# KiemSoat.net
KiCad netlist of a schematic drawn in Altium Designer
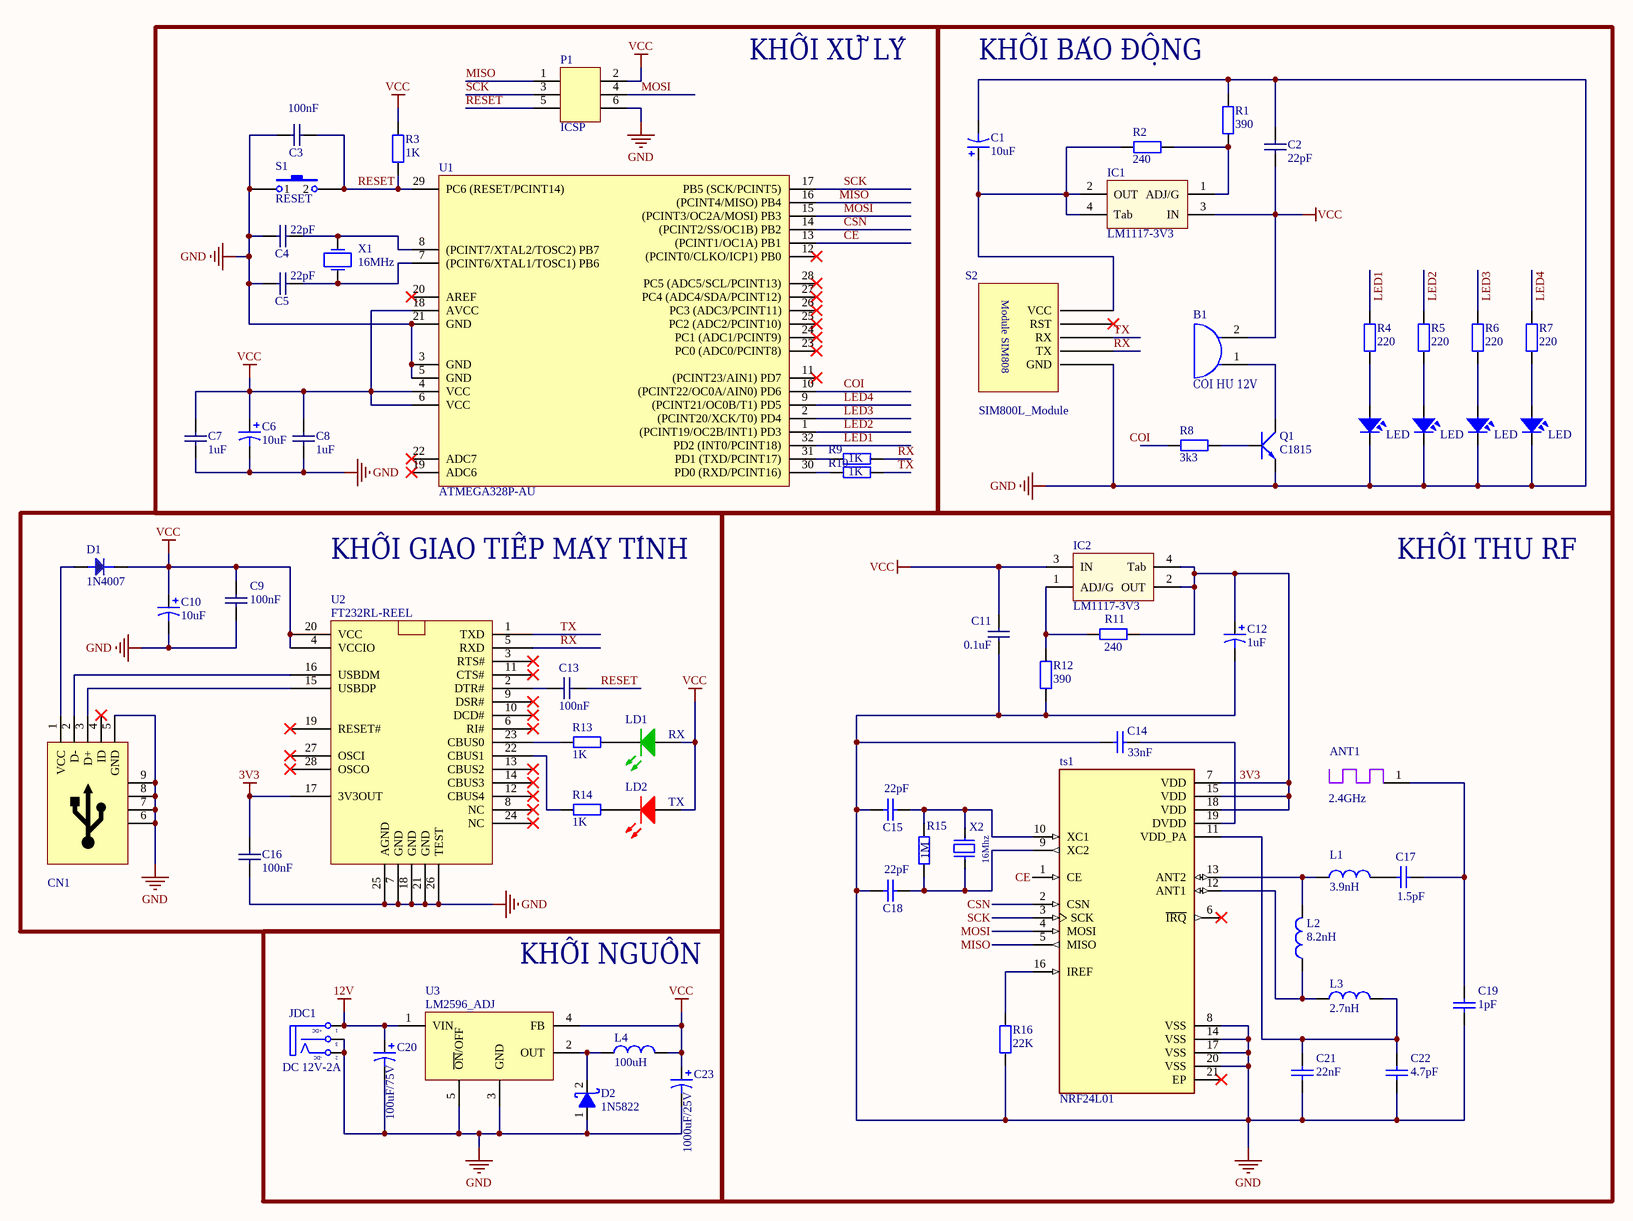
[diagram p0: KiemSoat.SchDoc]

(export (version "E")
  (design (tool "Eeschema 10.0.6"))
  (components
    (comp (ref "ANT1")
      (value "2.4GHz")
      (footprint "PATCH ANTEN 2.45GHZ")
      (description "PCB ANTENNA 2.45GHZ")
      (libsource (lib "BYTECH_HW_LIB_2019 (1)") (part "PCB antenna 2.45GHZ"))
    )
    (comp (ref "B1")
      (value "CÒI HÚ 12V")
      (footprint "Buzzer")
      (description "Buzzer")
      (libsource (lib "Cty1") (part "BUZZER"))
    )
    (comp (ref "C1")
      (value "10uF")
      (footprint "CAP_0805")
      (description "Polarized Capacitor (Axial)")
      (fields (field (name "PUBLISHER") "Altium Limited"))
      (libsource (lib "My Library") (part "Cap Pol 5mm"))
    )
    (comp (ref "C2")
      (value "22pF")
      (footprint "thuvien_altium:CAPC0805")
      (description "capacitor non polar")
      (libsource (lib "thuvien_altium") (part "capacitor_non_polar"))
    )
    (comp (ref "C3")
      (value "100nF")
      (footprint "thuvien_altium:CAPC0805")
      (description "capacitor non polar")
      (libsource (lib "thuvien_altium") (part "capacitor_non_polar"))
    )
    (comp (ref "C4")
      (value "22pF")
      (footprint "thuvien_altium:CAPC0805")
      (description "capacitor non polar")
      (libsource (lib "thuvien_altium") (part "capacitor_non_polar"))
    )
    (comp (ref "C5")
      (value "22pF")
      (footprint "thuvien_altium:CAPC0805")
      (description "capacitor non polar")
      (libsource (lib "thuvien_altium") (part "capacitor_non_polar"))
    )
    (comp (ref "C6")
      (value "10uF")
      (footprint "thuvien_altium:CAP1206_TANTALUM_YELLOW")
      (description "CAP TANT 10UF 16V 10% 1206")
      (fields (field (name "TOLERANCE") "±10%"))
      (libsource (lib "thuvien_altium") (part "T491A106K016AT"))
    )
    (comp (ref "C7")
      (value "1uF")
      (footprint "thuvien_altium:CAP0603")
      (description "capacitor non polar")
      (libsource (lib "thuvien_altium") (part "capacitor_non_polar"))
    )
    (comp (ref "C8")
      (value "1uF")
      (footprint "thuvien_altium:CAP0603")
      (description "capacitor non polar")
      (libsource (lib "thuvien_altium") (part "capacitor_non_polar"))
    )
    (comp (ref "C9")
      (value "100nF")
      (footprint "thuvien_altium:CAP0603")
      (description "capacitor non polar")
      (libsource (lib "thuvien_altium") (part "capacitor_non_polar"))
    )
    (comp (ref "C10")
      (value "10uF")
      (footprint "thuvien_altium:CAP1206_TANTALUM_YELLOW")
      (description "CAP TANT 10UF 16V 10% 1206")
      (fields (field (name "TOLERANCE") "±10%"))
      (libsource (lib "thuvien_altium") (part "T491A106K016AT"))
    )
    (comp (ref "C11")
      (value "0.1uF")
      (footprint "thuvien_altium:CAPC0805")
      (description "capacitor non polar")
      (libsource (lib "thuvien_altium") (part "capacitor_non_polar"))
    )
    (comp (ref "C12")
      (value "1uF")
      (footprint "CAP_0805")
      (description "Polarized Capacitor (Axial)")
      (fields (field (name "PUBLISHER") "Altium Limited"))
      (libsource (lib "My Library") (part "Cap Pol 5mm"))
    )
    (comp (ref "C13")
      (value "100nF")
      (footprint "thuvien_altium:CAP0603")
      (description "capacitor non polar")
      (libsource (lib "thuvien_altium") (part "capacitor_non_polar"))
    )
    (comp (ref "C14")
      (value "33nF")
      (footprint "CAPC0805")
      (description "Capacitor")
      (fields (field (name "PUBLISHER") "Altium Limited"))
      (libsource (lib "My Library") (part "CapCeramic"))
    )
    (comp (ref "C15")
      (value "22pF")
      (footprint "CAPC0805")
      (description "Capacitor")
      (fields (field (name "PUBLISHER") "Altium Limited"))
      (libsource (lib "My Library") (part "CapCeramic"))
    )
    (comp (ref "C16")
      (value "100nF")
      (footprint "thuvien_altium:CAP0603")
      (description "capacitor non polar")
      (libsource (lib "thuvien_altium") (part "capacitor_non_polar"))
    )
    (comp (ref "C17")
      (value "1.5pF")
      (footprint "CAPC0805")
      (description "Capacitor")
      (fields (field (name "PUBLISHER") "Altium Limited"))
      (libsource (lib "My Library") (part "CapCeramic"))
    )
    (comp (ref "C18")
      (value "22pF")
      (footprint "CAPC0805")
      (description "Capacitor")
      (fields (field (name "PUBLISHER") "Altium Limited"))
      (libsource (lib "My Library") (part "CapCeramic"))
    )
    (comp (ref "C19")
      (value "1pF")
      (footprint "CAPC0805")
      (description "Capacitor")
      (fields (field (name "PUBLISHER") "Altium Limited"))
      (libsource (lib "My Library") (part "CapCeramic"))
    )
    (comp (ref "C20")
      (value "100uF/75V")
      (footprint "CAP-ALU-SMD-G")
      (description "Polarized Capacitor (Axial)")
      (fields (field (name "PUBLISHER") "Altium Limited"))
      (libsource (lib "My Library") (part "Cap Pol 5mm"))
    )
    (comp (ref "C21")
      (value "22nF")
      (footprint "CAPC0805")
      (description "Capacitor")
      (fields (field (name "PUBLISHER") "Altium Limited"))
      (libsource (lib "My Library") (part "CapCeramic"))
    )
    (comp (ref "C22")
      (value "4.7pF")
      (footprint "CAPC0805")
      (description "Capacitor")
      (fields (field (name "PUBLISHER") "Altium Limited"))
      (libsource (lib "My Library") (part "CapCeramic"))
    )
    (comp (ref "C23")
      (value "1000uF/25V")
      (footprint "CAP-ALU-SMD-G")
      (description "Polarized Capacitor (Axial)")
      (fields (field (name "PUBLISHER") "Altium Limited"))
      (libsource (lib "My Library") (part "Cap Pol 5mm"))
    )
    (comp (ref "CN1")
      (value "690-005-299-043")
      (footprint "thuvien_altium:USB-B-MINI_690-005-299-043")
      (description "CONN MINI USB RCPT RA TYPE B SMD")
      (fields (field (name "MANUFACTURER") "EDAC Inc."))
      (libsource (lib "thuvien_altium") (part "USB_690-005-299-043"))
    )
    (comp (ref "D1")
      (value "1N4007")
      (footprint "thuvien_altium:DO-214AC")
      (description "diode")
      (libsource (lib "thuvien_altium") (part "diode"))
    )
    (comp (ref "D2")
      (value "1N5822")
      (footprint "SM-DIODE")
      (description "Schottky Rectifiers")
      (libsource (lib "My Library") (part "1N5822"))
    )
    (comp (ref "IC1")
      (value "LM1117-3V3")
      (footprint "SOT223-4N")
      (description "3v3")
      (libsource (lib "") (part "LM1117_1_1"))
    )
    (comp (ref "IC2")
      (value "LM1117-3V3")
      (footprint "SOT223-4N")
      (description "3v3")
      (libsource (lib "[Devzone.vn]_SchLibrary") (part "LM1117_1"))
    )
    (comp (ref "JDC1")
      (value "DC 12V-2A")
      (footprint "DC-IN")
      (description "Jac DC input")
      (libsource (lib "[Devzone.vn]_SchLibrary") (part "DCIN"))
    )
    (comp (ref "L1")
      (value "3.9nH")
      (footprint "INDC_DR127-1")
      (description "Inductor")
      (libsource (lib "My Library") (part "L1"))
    )
    (comp (ref "L2")
      (value "8.2nH")
      (footprint "INDC_DR127-1")
      (description "Inductor")
      (libsource (lib "My Library") (part "L1"))
    )
    (comp (ref "L3")
      (value "2.7nH")
      (footprint "INDC_DR127-1")
      (description "Inductor")
      (libsource (lib "My Library") (part "L1"))
    )
    (comp (ref "L4")
      (value "100uH")
      (footprint "Inductor_SMD")
      (description "Inductor")
      (libsource (lib "My Library") (part "Inductor"))
    )
    (comp (ref "LD1")
      (value "RX")
      (footprint "thuvien_altium:LED_SMD0603_GREEN")
      (description "LED GREEN CLEAR 0603 SMD")
      (libsource (lib "thuvien_altium") (part "LED_LTST-C191KGKT"))
    )
    (comp (ref "LD2")
      (value "TX")
      (footprint "thuvien_altium:LED_SMD0603_RED")
      (description "LED RED CLEAR 0603 SMD")
      (fields
        (field (name "MANUFACTURER") "Lite-On Inc.")
        (field (name "MANUFACTURER PART NUMBER") "LTST-C191KRKT")
      )
      (libsource (lib "thuvien_altium") (part "LED_LTST-C191KRKT"))
    )
    (comp (ref "LED1")
      (value "LED")
      (footprint "LED-RED-0805")
      (description "LED Single colour Green and Red")
      (libsource (lib "My Library") (part "LED"))
    )
    (comp (ref "LED2")
      (value "LED")
      (footprint "LED-RED-0805")
      (description "LED Single colour Green and Red")
      (libsource (lib "My Library") (part "LED"))
    )
    (comp (ref "LED3")
      (value "LED")
      (footprint "LED-RED-0805")
      (description "LED Single colour Green and Red")
      (libsource (lib "My Library") (part "LED"))
    )
    (comp (ref "LED4")
      (value "LED")
      (footprint "LED-RED-0805")
      (description "LED Single colour Green and Red")
      (libsource (lib "My Library") (part "LED"))
    )
    (comp (ref "P1")
      (value "ICSP")
      (footprint "thuvien_altium:HDR_M_2X3_2.54")
      (libsource (lib "thuvien_altium") (part "header_2x3pins"))
    )
    (comp (ref "Q1")
      (value "C1815")
      (footprint "SOT23B")
      (description "NPN 600mW, ECB")
      (libsource (lib "syhaunguyen") (part "C1815"))
    )
    (comp (ref "R1")
      (value "390")
      (footprint "RES_SMD_0805")
      (description "Resistor 1/4W")
      (libsource (lib "My Library") (part "R1/4W"))
    )
    (comp (ref "R2")
      (value "240")
      (footprint "RES_SMD_0805")
      (description "Resistor 1/4W")
      (libsource (lib "My Library") (part "R1/4W"))
    )
    (comp (ref "R3")
      (value "1K")
      (footprint "RES_SMD_0805")
      (description "Resistor 1/4W")
      (libsource (lib "My Library") (part "R1/4W"))
    )
    (comp (ref "R4")
      (value "220")
      (footprint "RES_SMD_0805")
      (description "Resistor 1/4W")
      (libsource (lib "My Library") (part "R1/4W"))
    )
    (comp (ref "R5")
      (value "220")
      (footprint "RES_SMD_0805")
      (description "Resistor 1/4W")
      (libsource (lib "My Library") (part "R1/4W"))
    )
    (comp (ref "R6")
      (value "220")
      (footprint "RES_SMD_0805")
      (description "Resistor 1/4W")
      (libsource (lib "My Library") (part "R1/4W"))
    )
    (comp (ref "R7")
      (value "220")
      (footprint "RES_SMD_0805")
      (description "Resistor 1/4W")
      (libsource (lib "My Library") (part "R1/4W"))
    )
    (comp (ref "R8")
      (value "3k3")
      (footprint "RES_SMD_0805")
      (description "Resistor 1/4W")
      (libsource (lib "My Library") (part "R1/4W"))
    )
    (comp (ref "R9")
      (value "1K")
      (footprint "RES_SMD_0805")
      (description "Resistor 1/4W")
      (libsource (lib "My Library") (part "R1/4W"))
    )
    (comp (ref "R10")
      (value "1K")
      (footprint "RES_SMD_0805")
      (description "Resistor 1/4W")
      (libsource (lib "My Library") (part "R1/4W"))
    )
    (comp (ref "R11")
      (value "240")
      (footprint "RES_SMD_0805")
      (description "Resistor 1/4W")
      (libsource (lib "My Library") (part "R1/4W"))
    )
    (comp (ref "R12")
      (value "390")
      (footprint "RES_SMD_0805")
      (description "Resistor 1/4W")
      (libsource (lib "My Library") (part "R1/4W"))
    )
    (comp (ref "R13")
      (value "1K")
      (footprint "RES_SMD_0805")
      (description "Resistor 1/4W")
      (libsource (lib "My Library") (part "R1/4W"))
    )
    (comp (ref "R14")
      (value "1K")
      (footprint "RES_SMD_0805")
      (description "Resistor 1/4W")
      (libsource (lib "My Library") (part "R1/4W"))
    )
    (comp (ref "R15")
      (value "1M")
      (footprint "RES_SMD_0805")
      (description "Resistor 1/4W")
      (libsource (lib "My Library") (part "R1/4W"))
    )
    (comp (ref "R16")
      (value "22K")
      (footprint "RES_SMD_0805")
      (description "Resistor 1/4W")
      (libsource (lib "My Library") (part "R1/4W"))
    )
    (comp (ref "S1")
      (value "RESET")
      (footprint "thuvien_altium:SW_B3U-1000P")
      (description "Switch")
      (fields (field (name "PUBLISHER") "Altium Limited"))
      (libsource (lib "thuvien_altium") (part "SW-PB-2pin"))
    )
    (comp (ref "S2")
      (value "SIM800L_Module")
      (footprint "SIM808_Module")
      (libsource (lib "SIM808_SCH") (part "SIM800L_Module"))
    )
    (comp (ref "ts1")
      (value "NRF24L01")
      (footprint "QFN50P400X400X95-21N")
      (description "IC RF TxRx Only General ISM > 1GHZ 2.4GHz 20-VFQFN Exposed Pad")
      (fields (field (name "MP") "NRF24L01+") (field (name "MF") "Nordic Semiconductor"))
      (libsource (lib "NRF24L01-SE") (part "NRF24L01"))
    )
    (comp (ref "U1")
      (value "ATMEGA328P-AU")
      (footprint "thuvien_altium:TQFP-32")
      (description "AVR AVR® ATmega Microcontroller IC 8-Bit 20MHz 32KB (16K x 16) FLASH 32-TQFP (7x7)")
      (libsource (lib "thuvien_altium") (part "atmega328p-au"))
    )
    (comp (ref "U2")
      (value "FT232RL-REEL")
      (footprint "SSOP28")
      (description "USB Interface IC USB to Serial UART Enhanced IC SSOP-28")
      (fields (field (name "MANUFACTURER") "FTDI"))
      (libsource (lib "thuvien_altium") (part "FT232RL-REEL"))
    )
    (comp (ref "U3")
      (value "LM2596_ADJ")
      (footprint "thuvien_altium:TO263-5")
      (libsource (lib "thuvien_altium") (part "LM2596_ADJ"))
    )
    (comp (ref "X1")
      (value "16MHz")
      (footprint "XTAL_SMD_HC-49S")
      (description "CRYSTAL 16.0000MHZ 12PF T/H")
      (fields
        (field (name "MANUFACTURER") "TXC CORPORATION")
        (field (name "MANUFACTURER PART NUMBER") "9B-16.000MAAE-B")
      )
      (libsource (lib "Indruino") (part "XTAL_9B-16.000MAAE-B"))
    )
    (comp (ref "X2")
      (value "16Mhz")
      (footprint "XTAL_SMD_HC-49S")
      (description "Crystal For all Crystal 2pin.")
      (libsource (lib "My Library") (part "XT2"))
    )
  )
  (nets
    (net (code "1") (name "/CE") (class "Default")
      (node (ref "U1") (pin "13") (pinfunction "(PCINT1/OC1A)_PB1_13") (pintype "power_in"))
      (node (ref "ts1") (pin "1") (pinfunction "CE_1") (pintype "input"))
    )
    (net (code "2") (name "/COI") (class "Default")
      (node (ref "R8") (pin "1") (pinfunction "1_1") (pintype "passive"))
      (node (ref "U1") (pin "10") (pinfunction "(PCINT22/OC0A/AIN0)_PD6_10") (pintype "power_in"))
    )
    (net (code "3") (name "/CSN") (class "Default")
      (node (ref "U1") (pin "14") (pinfunction "(PCINT2/SS/OC1B)_PB2_14") (pintype "power_in"))
      (node (ref "ts1") (pin "2") (pinfunction "CSN_2") (pintype "input"))
    )
    (net (code "4") (name "/LED1") (class "Default")
      (node (ref "R4") (pin "1") (pinfunction "1_1") (pintype "passive"))
      (node (ref "U1") (pin "32") (pinfunction "PD2_(INT0/PCINT18)_32") (pintype "power_in"))
    )
    (net (code "5") (name "/LED2") (class "Default")
      (node (ref "R5") (pin "1") (pinfunction "1_1") (pintype "passive"))
      (node (ref "U1") (pin "1") (pinfunction "(PCINT19/OC2B/INT1)_PD3_1") (pintype "power_in"))
    )
    (net (code "6") (name "/LED3") (class "Default")
      (node (ref "R6") (pin "1") (pinfunction "1_1") (pintype "passive"))
      (node (ref "U1") (pin "2") (pinfunction "(PCINT20/XCK/T0)_PD4_2") (pintype "power_in"))
    )
    (net (code "7") (name "/LED4") (class "Default")
      (node (ref "R7") (pin "1") (pinfunction "1_1") (pintype "passive"))
      (node (ref "U1") (pin "9") (pinfunction "(PCINT21/OC0B/T1)_PD5_9") (pintype "power_in"))
    )
    (net (code "8") (name "/MISO") (class "Default")
      (node (ref "P1") (pin "1") (pinfunction "1_1") (pintype "power_in"))
      (node (ref "U1") (pin "16") (pinfunction "(PCINT4/MISO)_PB4_16") (pintype "power_in"))
      (node (ref "ts1") (pin "5") (pinfunction "MISO_5") (pintype "output"))
    )
    (net (code "9") (name "/MOSI") (class "Default")
      (node (ref "P1") (pin "4") (pinfunction "4_4") (pintype "power_in"))
      (node (ref "U1") (pin "15") (pinfunction "(PCINT3/OC2A/MOSI)_PB3_15") (pintype "power_in"))
      (node (ref "ts1") (pin "4") (pinfunction "MOSI_4") (pintype "input"))
    )
    (net (code "10") (name "/RESET") (class "Default")
      (node (ref "C13") (pin "2") (pinfunction "2_2") (pintype "power_in"))
      (node (ref "C3") (pin "2") (pinfunction "2_2") (pintype "power_in"))
      (node (ref "P1") (pin "5") (pinfunction "5_5") (pintype "power_in"))
      (node (ref "R3") (pin "1") (pinfunction "1_1") (pintype "passive"))
      (node (ref "S1") (pin "2") (pinfunction "2_2") (pintype "passive"))
      (node (ref "U1") (pin "29") (pinfunction "PC6_(RESET/PCINT14)_29") (pintype "power_in"))
    )
    (net (code "11") (name "/RX") (class "Default")
      (node (ref "R9") (pin "2") (pinfunction "2_2") (pintype "passive"))
      (node (ref "S2") (pin "4") (pinfunction "TX_4") (pintype "passive"))
      (node (ref "U2") (pin "5") (pinfunction "RXD_5") (pintype "passive"))
    )
    (net (code "12") (name "/SCK") (class "Default")
      (node (ref "P1") (pin "3") (pinfunction "3_3") (pintype "power_in"))
      (node (ref "U1") (pin "17") (pinfunction "PB5_(SCK/PCINT5)_17") (pintype "power_in"))
      (node (ref "ts1") (pin "3") (pinfunction "SCK_3") (pintype "input"))
    )
    (net (code "13") (name "/TX") (class "Default")
      (node (ref "R10") (pin "2") (pinfunction "2_2") (pintype "passive"))
      (node (ref "S2") (pin "3") (pinfunction "RX_3") (pintype "passive"))
      (node (ref "U2") (pin "1") (pinfunction "TXD_1") (pintype "passive"))
    )
    (net (code "14") (name "3V3") (class "Default")
      (node (ref "C12") (pin "1") (pinfunction "1_1") (pintype "passive"))
      (node (ref "C16") (pin "1") (pinfunction "1_1") (pintype "power_in"))
      (node (ref "IC2") (pin "2") (pinfunction "OUT_2") (pintype "passive"))
      (node (ref "IC2") (pin "4") (pinfunction "Tab_4") (pintype "passive"))
      (node (ref "R11") (pin "1") (pinfunction "1_1") (pintype "passive"))
      (node (ref "U2") (pin "17") (pinfunction "3V3OUT_17") (pintype "passive"))
      (node (ref "ts1") (pin "15") (pinfunction "VDD_15") (pintype "power_in"))
      (node (ref "ts1") (pin "18") (pinfunction "VDD_18") (pintype "power_in"))
      (node (ref "ts1") (pin "7") (pinfunction "VDD_7") (pintype "power_in"))
    )
    (net (code "15") (name "12V") (class "Default")
      (node (ref "C20") (pin "1") (pinfunction "1_1") (pintype "passive"))
      (node (ref "JDC1") (pin "1") (pinfunction "T_1") (pintype "passive"))
      (node (ref "U3") (pin "1") (pinfunction "VIN_1") (pintype "power_in"))
    )
    (net (code "16") (name "GND") (class "Default")
      (node (ref "C1") (pin "2") (pinfunction "2_2") (pintype "passive"))
      (node (ref "C10") (pin "2") (pinfunction "2_2") (pintype "passive"))
      (node (ref "C11") (pin "1") (pinfunction "1_1") (pintype "power_in"))
      (node (ref "C12") (pin "2") (pinfunction "2_2") (pintype "passive"))
      (node (ref "C14") (pin "1") (pinfunction "1_1") (pintype "passive"))
      (node (ref "C15") (pin "1") (pinfunction "1_1") (pintype "passive"))
      (node (ref "C16") (pin "2") (pinfunction "2_2") (pintype "power_in"))
      (node (ref "C18") (pin "1") (pinfunction "1_1") (pintype "passive"))
      (node (ref "C19") (pin "1") (pinfunction "1_1") (pintype "passive"))
      (node (ref "C2") (pin "1") (pinfunction "1_1") (pintype "power_in"))
      (node (ref "C20") (pin "2") (pinfunction "2_2") (pintype "passive"))
      (node (ref "C21") (pin "1") (pinfunction "1_1") (pintype "passive"))
      (node (ref "C22") (pin "1") (pinfunction "1_1") (pintype "passive"))
      (node (ref "C23") (pin "2") (pinfunction "2_2") (pintype "passive"))
      (node (ref "C3") (pin "1") (pinfunction "1_1") (pintype "power_in"))
      (node (ref "C4") (pin "1") (pinfunction "1_1") (pintype "power_in"))
      (node (ref "C5") (pin "1") (pinfunction "1_1") (pintype "power_in"))
      (node (ref "C6") (pin "2") (pinfunction "2_2") (pintype "passive"))
      (node (ref "C7") (pin "2") (pinfunction "2_2") (pintype "power_in"))
      (node (ref "C8") (pin "2") (pinfunction "2_2") (pintype "power_in"))
      (node (ref "C9") (pin "2") (pinfunction "2_2") (pintype "power_in"))
      (node (ref "CN1") (pin "5") (pinfunction "GND_5") (pintype "passive"))
      (node (ref "CN1") (pin "6") (pinfunction "6_6") (pintype "power_in"))
      (node (ref "CN1") (pin "7") (pinfunction "7_7") (pintype "power_in"))
      (node (ref "CN1") (pin "8") (pinfunction "8_8") (pintype "power_in"))
      (node (ref "CN1") (pin "9") (pinfunction "9_9") (pintype "power_in"))
      (node (ref "D2") (pin "1") (pinfunction "A_1") (pintype "passive"))
      (node (ref "JDC1") (pin "2") (pinfunction "TN_2") (pintype "passive"))
      (node (ref "JDC1") (pin "3") (pinfunction "S_3") (pintype "power_in"))
      (node (ref "LED1") (pin "2") (pinfunction "2_2") (pintype "passive"))
      (node (ref "LED2") (pin "2") (pinfunction "2_2") (pintype "passive"))
      (node (ref "LED3") (pin "2") (pinfunction "2_2") (pintype "passive"))
      (node (ref "LED4") (pin "2") (pinfunction "2_2") (pintype "passive"))
      (node (ref "P1") (pin "6") (pinfunction "6_6") (pintype "power_in"))
      (node (ref "Q1") (pin "1") (pinfunction "E_1") (pintype "passive"))
      (node (ref "R1") (pin "1") (pinfunction "1_1") (pintype "passive"))
      (node (ref "R12") (pin "1") (pinfunction "1_1") (pintype "passive"))
      (node (ref "R16") (pin "1") (pinfunction "1_1") (pintype "passive"))
      (node (ref "S1") (pin "1") (pinfunction "1_1") (pintype "passive"))
      (node (ref "S2") (pin "5") (pinfunction "GND_5") (pintype "passive"))
      (node (ref "U1") (pin "21") (pinfunction "GND_21") (pintype "power_in"))
      (node (ref "U1") (pin "3") (pinfunction "GND_3") (pintype "power_in"))
      (node (ref "U1") (pin "5") (pinfunction "GND_5") (pintype "power_in"))
      (node (ref "U2") (pin "18") (pinfunction "GND_18") (pintype "passive"))
      (node (ref "U2") (pin "21") (pinfunction "GND_21") (pintype "passive"))
      (node (ref "U2") (pin "25") (pinfunction "AGND_25") (pintype "passive"))
      (node (ref "U2") (pin "26") (pinfunction "TEST_26") (pintype "passive"))
      (node (ref "U2") (pin "7") (pinfunction "GND_7") (pintype "passive"))
      (node (ref "U3") (pin "3") (pinfunction "GND_3") (pintype "power_in"))
      (node (ref "U3") (pin "5") (pinfunction "~{ON}/OFF_5") (pintype "power_in"))
      (node (ref "ts1") (pin "14") (pinfunction "VSS_14") (pintype "power_in"))
      (node (ref "ts1") (pin "17") (pinfunction "VSS_17") (pintype "power_in"))
      (node (ref "ts1") (pin "20") (pinfunction "VSS_20") (pintype "power_in"))
      (node (ref "ts1") (pin "8") (pinfunction "VSS_8") (pintype "power_in"))
    )
    (net (code "17") (name "Net-(ANT1-ANT)") (class "Default")
      (node (ref "ANT1") (pin "1") (pinfunction "ANT_1") (pintype "passive"))
      (node (ref "C17") (pin "2") (pinfunction "2_2") (pintype "passive"))
      (node (ref "C19") (pin "2") (pinfunction "2_2") (pintype "passive"))
    )
    (net (code "18") (name "Net-(B1-A)") (class "Default")
      (node (ref "B1") (pin "1") (pinfunction "A_1") (pintype "passive"))
      (node (ref "Q1") (pin "2") (pinfunction "C_2") (pintype "passive"))
    )
    (net (code "19") (name "Net-(C17-Pad1)") (class "Default")
      (node (ref "C17") (pin "1") (pinfunction "1_1") (pintype "passive"))
      (node (ref "L1") (pin "2") (pinfunction "2_2") (pintype "passive"))
    )
    (net (code "20") (name "Net-(CN1-D+)") (class "Default")
      (node (ref "CN1") (pin "3") (pinfunction "D+_3") (pintype "passive"))
      (node (ref "U2") (pin "15") (pinfunction "USBDP_15") (pintype "passive"))
    )
    (net (code "21") (name "Net-(CN1-D-)") (class "Default")
      (node (ref "CN1") (pin "2") (pinfunction "D-_2") (pintype "passive"))
      (node (ref "U2") (pin "16") (pinfunction "USBDM_16") (pintype "passive"))
    )
    (net (code "22") (name "Net-(CN1-VCC)") (class "Default")
      (node (ref "CN1") (pin "1") (pinfunction "VCC_1") (pintype "passive"))
      (node (ref "D1") (pin "1") (pinfunction "A_1") (pintype "power_in"))
    )
    (net (code "23") (name "Net-(D2-K)") (class "Default")
      (node (ref "D2") (pin "2") (pinfunction "K_2") (pintype "passive"))
      (node (ref "L4") (pin "1") (pinfunction "1_1") (pintype "passive"))
      (node (ref "U3") (pin "2") (pinfunction "OUT_2") (pintype "power_in"))
    )
    (net (code "24") (name "Net-(IC1-ADJ{slash}G)") (class "Default")
      (node (ref "IC1") (pin "1") (pinfunction "ADJ/G_1") (pintype "passive"))
      (node (ref "R1") (pin "2") (pinfunction "2_2") (pintype "passive"))
      (node (ref "R2") (pin "2") (pinfunction "2_2") (pintype "passive"))
    )
    (net (code "25") (name "Net-(IC1-OUT)") (class "Default")
      (node (ref "C1") (pin "1") (pinfunction "1_1") (pintype "passive"))
      (node (ref "IC1") (pin "2") (pinfunction "OUT_2") (pintype "passive"))
      (node (ref "IC1") (pin "4") (pinfunction "Tab_4") (pintype "passive"))
      (node (ref "R2") (pin "1") (pinfunction "1_1") (pintype "passive"))
      (node (ref "S2") (pin "1") (pinfunction "VCC_1") (pintype "passive"))
    )
    (net (code "26") (name "Net-(IC2-ADJ{slash}G)") (class "Default")
      (node (ref "IC2") (pin "1") (pinfunction "ADJ/G_1") (pintype "passive"))
      (node (ref "R11") (pin "2") (pinfunction "2_2") (pintype "passive"))
      (node (ref "R12") (pin "2") (pinfunction "2_2") (pintype "passive"))
    )
    (net (code "27") (name "Net-(LD1-K)") (class "Default")
      (node (ref "LD1") (pin "2") (pinfunction "K_2") (pintype "passive"))
      (node (ref "R13") (pin "2") (pinfunction "2_2") (pintype "passive"))
    )
    (net (code "28") (name "Net-(LD2-K)") (class "Default")
      (node (ref "LD2") (pin "2") (pinfunction "K_2") (pintype "passive"))
      (node (ref "R14") (pin "2") (pinfunction "2_2") (pintype "passive"))
    )
    (net (code "29") (name "Net-(LED1-Pad1)") (class "Default")
      (node (ref "LED1") (pin "1") (pinfunction "1_1") (pintype "passive"))
      (node (ref "R4") (pin "2") (pinfunction "2_2") (pintype "passive"))
    )
    (net (code "30") (name "Net-(LED2-Pad1)") (class "Default")
      (node (ref "LED2") (pin "1") (pinfunction "1_1") (pintype "passive"))
      (node (ref "R5") (pin "2") (pinfunction "2_2") (pintype "passive"))
    )
    (net (code "31") (name "Net-(LED3-Pad1)") (class "Default")
      (node (ref "LED3") (pin "1") (pinfunction "1_1") (pintype "passive"))
      (node (ref "R6") (pin "2") (pinfunction "2_2") (pintype "passive"))
    )
    (net (code "32") (name "Net-(LED4-Pad1)") (class "Default")
      (node (ref "LED4") (pin "1") (pinfunction "1_1") (pintype "passive"))
      (node (ref "R7") (pin "2") (pinfunction "2_2") (pintype "passive"))
    )
    (net (code "33") (name "Net-(Q1-B)") (class "Default")
      (node (ref "Q1") (pin "3") (pinfunction "B_3") (pintype "passive"))
      (node (ref "R8") (pin "2") (pinfunction "2_2") (pintype "passive"))
    )
    (net (code "34") (name "Net-(U1-(PCINT6{slash}XTAL1{slash}TOSC1)_PB6)") (class "Default")
      (node (ref "C5") (pin "2") (pinfunction "2_2") (pintype "power_in"))
      (node (ref "U1") (pin "7") (pinfunction "(PCINT6/XTAL1/TOSC1)_PB6_7") (pintype "power_in"))
      (node (ref "X1") (pin "1") (pinfunction "OSC1_1") (pintype "passive"))
    )
    (net (code "35") (name "Net-(U1-(PCINT7{slash}XTAL2{slash}TOSC2)_PB7)") (class "Default")
      (node (ref "C4") (pin "2") (pinfunction "2_2") (pintype "power_in"))
      (node (ref "U1") (pin "8") (pinfunction "(PCINT7/XTAL2/TOSC2)_PB7_8") (pintype "power_in"))
      (node (ref "X1") (pin "2") (pinfunction "OSC2_2") (pintype "passive"))
    )
    (net (code "36") (name "Net-(U1-PD0_(RXD{slash}PCINT16))") (class "Default")
      (node (ref "R10") (pin "1") (pinfunction "1_1") (pintype "passive"))
      (node (ref "U1") (pin "30") (pinfunction "PD0_(RXD/PCINT16)_30") (pintype "power_in"))
    )
    (net (code "37") (name "Net-(U1-PD1_(TXD{slash}PCINT17))") (class "Default")
      (node (ref "R9") (pin "1") (pinfunction "1_1") (pintype "passive"))
      (node (ref "U1") (pin "31") (pinfunction "PD1_(TXD/PCINT17)_31") (pintype "power_in"))
    )
    (net (code "38") (name "Net-(U2-CBUS0)") (class "Default")
      (node (ref "R13") (pin "1") (pinfunction "1_1") (pintype "passive"))
      (node (ref "U2") (pin "23") (pinfunction "CBUS0_23") (pintype "passive"))
    )
    (net (code "39") (name "Net-(U2-CBUS1)") (class "Default")
      (node (ref "R14") (pin "1") (pinfunction "1_1") (pintype "passive"))
      (node (ref "U2") (pin "22") (pinfunction "CBUS1_22") (pintype "passive"))
    )
    (net (code "40") (name "Net-(U2-DTR#)") (class "Default")
      (node (ref "C13") (pin "1") (pinfunction "1_1") (pintype "power_in"))
      (node (ref "U2") (pin "2") (pinfunction "DTR#_2") (pintype "passive"))
    )
    (net (code "41") (name "Net-(ts1-ANT1)") (class "Default")
      (node (ref "L2") (pin "1") (pinfunction "1_1") (pintype "passive"))
      (node (ref "L3") (pin "1") (pinfunction "1_1") (pintype "passive"))
      (node (ref "ts1") (pin "12") (pinfunction "ANT1_12") (pintype "bidirectional"))
    )
    (net (code "42") (name "Net-(ts1-ANT2)") (class "Default")
      (node (ref "L1") (pin "1") (pinfunction "1_1") (pintype "passive"))
      (node (ref "L2") (pin "2") (pinfunction "2_2") (pintype "passive"))
      (node (ref "ts1") (pin "13") (pinfunction "ANT2_13") (pintype "bidirectional"))
    )
    (net (code "43") (name "Net-(ts1-DVDD)") (class "Default")
      (node (ref "C14") (pin "2") (pinfunction "2_2") (pintype "passive"))
      (node (ref "ts1") (pin "19") (pinfunction "DVDD_19") (pintype "power_in"))
    )
    (net (code "44") (name "Net-(ts1-IREF)") (class "Default")
      (node (ref "R16") (pin "2") (pinfunction "2_2") (pintype "passive"))
      (node (ref "ts1") (pin "16") (pinfunction "IREF_16") (pintype "input"))
    )
    (net (code "45") (name "Net-(ts1-VDD_PA)") (class "Default")
      (node (ref "C21") (pin "2") (pinfunction "2_2") (pintype "passive"))
      (node (ref "C22") (pin "2") (pinfunction "2_2") (pintype "passive"))
      (node (ref "L3") (pin "2") (pinfunction "2_2") (pintype "passive"))
      (node (ref "ts1") (pin "11") (pinfunction "VDD_PA_11") (pintype "power_in"))
    )
    (net (code "46") (name "Net-(ts1-XC1)") (class "Default")
      (node (ref "C15") (pin "2") (pinfunction "2_2") (pintype "passive"))
      (node (ref "R15") (pin "2") (pinfunction "2_2") (pintype "passive"))
      (node (ref "X2") (pin "1") (pinfunction "1_1") (pintype "passive"))
      (node (ref "ts1") (pin "10") (pinfunction "XC1_10") (pintype "input"))
    )
    (net (code "47") (name "Net-(ts1-XC2)") (class "Default")
      (node (ref "C18") (pin "2") (pinfunction "2_2") (pintype "passive"))
      (node (ref "R15") (pin "1") (pinfunction "1_1") (pintype "passive"))
      (node (ref "X2") (pin "2") (pinfunction "2_2") (pintype "passive"))
      (node (ref "ts1") (pin "9") (pinfunction "XC2_9") (pintype "output"))
    )
    (net (code "48") (name "VCC") (class "Default")
      (node (ref "B1") (pin "2") (pinfunction "B_2") (pintype "passive"))
      (node (ref "C10") (pin "1") (pinfunction "1_1") (pintype "passive"))
      (node (ref "C11") (pin "2") (pinfunction "2_2") (pintype "power_in"))
      (node (ref "C2") (pin "2") (pinfunction "2_2") (pintype "power_in"))
      (node (ref "C23") (pin "1") (pinfunction "1_1") (pintype "passive"))
      (node (ref "C6") (pin "1") (pinfunction "1_1") (pintype "passive"))
      (node (ref "C7") (pin "1") (pinfunction "1_1") (pintype "power_in"))
      (node (ref "C8") (pin "1") (pinfunction "1_1") (pintype "power_in"))
      (node (ref "C9") (pin "1") (pinfunction "1_1") (pintype "power_in"))
      (node (ref "D1") (pin "2") (pinfunction "K_2") (pintype "power_in"))
      (node (ref "IC1") (pin "3") (pinfunction "IN_3") (pintype "passive"))
      (node (ref "IC2") (pin "3") (pinfunction "IN_3") (pintype "passive"))
      (node (ref "L4") (pin "2") (pinfunction "2_2") (pintype "passive"))
      (node (ref "LD1") (pin "1") (pinfunction "A_1") (pintype "passive"))
      (node (ref "LD2") (pin "1") (pinfunction "A_1") (pintype "passive"))
      (node (ref "P1") (pin "2") (pinfunction "2_2") (pintype "power_in"))
      (node (ref "R3") (pin "2") (pinfunction "2_2") (pintype "passive"))
      (node (ref "U1") (pin "18") (pinfunction "AVCC_18") (pintype "power_in"))
      (node (ref "U1") (pin "4") (pinfunction "VCC_4") (pintype "power_in"))
      (node (ref "U1") (pin "6") (pinfunction "VCC_6") (pintype "power_in"))
      (node (ref "U2") (pin "20") (pinfunction "VCC_20") (pintype "passive"))
      (node (ref "U2") (pin "4") (pinfunction "VCCIO_4") (pintype "passive"))
      (node (ref "U3") (pin "4") (pinfunction "FB_4") (pintype "power_in"))
    )
    (net (code "49") (name "unconnected-(CN1-ID-Pad4)") (class "Default")
      (node (ref "CN1") (pin "4") (pinfunction "ID_4") (pintype "passive+no_connect"))
    )
    (net (code "50") (name "unconnected-(S2-RST-Pad2)") (class "Default")
      (node (ref "S2") (pin "2") (pinfunction "RST_2") (pintype "passive+no_connect"))
    )
    (net (code "51") (name "unconnected-(U1-(PCINT0{slash}CLKO{slash}ICP1)_PB0-Pad12)") (class "Default")
      (node (ref "U1") (pin "12") (pinfunction "(PCINT0/CLKO/ICP1)_PB0_12") (pintype "power_in+no_connect"))
    )
    (net (code "52") (name "unconnected-(U1-(PCINT23{slash}AIN1)_PD7-Pad11)") (class "Default")
      (node (ref "U1") (pin "11") (pinfunction "(PCINT23/AIN1)_PD7_11") (pintype "power_in+no_connect"))
    )
    (net (code "53") (name "unconnected-(U1-ADC6-Pad19)") (class "Default")
      (node (ref "U1") (pin "19") (pinfunction "ADC6_19") (pintype "power_in+no_connect"))
    )
    (net (code "54") (name "unconnected-(U1-ADC7-Pad22)") (class "Default")
      (node (ref "U1") (pin "22") (pinfunction "ADC7_22") (pintype "power_in+no_connect"))
    )
    (net (code "55") (name "unconnected-(U1-AREF-Pad20)") (class "Default")
      (node (ref "U1") (pin "20") (pinfunction "AREF_20") (pintype "power_in+no_connect"))
    )
    (net (code "56") (name "unconnected-(U1-PC0_(ADC0{slash}PCINT8)-Pad23)") (class "Default")
      (node (ref "U1") (pin "23") (pinfunction "PC0_(ADC0/PCINT8)_23") (pintype "power_in+no_connect"))
    )
    (net (code "57") (name "unconnected-(U1-PC1_(ADC1{slash}PCINT9)-Pad24)") (class "Default")
      (node (ref "U1") (pin "24") (pinfunction "PC1_(ADC1/PCINT9)_24") (pintype "power_in+no_connect"))
    )
    (net (code "58") (name "unconnected-(U1-PC2_(ADC2{slash}PCINT10)-Pad25)") (class "Default")
      (node (ref "U1") (pin "25") (pinfunction "PC2_(ADC2/PCINT10)_25") (pintype "power_in+no_connect"))
    )
    (net (code "59") (name "unconnected-(U1-PC3_(ADC3{slash}PCINT11)-Pad26)") (class "Default")
      (node (ref "U1") (pin "26") (pinfunction "PC3_(ADC3/PCINT11)_26") (pintype "power_in+no_connect"))
    )
    (net (code "60") (name "unconnected-(U1-PC4_(ADC4{slash}SDA{slash}PCINT12)-Pad27)") (class "Default")
      (node (ref "U1") (pin "27") (pinfunction "PC4_(ADC4/SDA/PCINT12)_27") (pintype "power_in+no_connect"))
    )
    (net (code "61") (name "unconnected-(U1-PC5_(ADC5{slash}SCL{slash}PCINT13)-Pad28)") (class "Default")
      (node (ref "U1") (pin "28") (pinfunction "PC5_(ADC5/SCL/PCINT13)_28") (pintype "power_in+no_connect"))
    )
    (net (code "62") (name "unconnected-(U2-CBUS2-Pad13)") (class "Default")
      (node (ref "U2") (pin "13") (pinfunction "CBUS2_13") (pintype "passive+no_connect"))
    )
    (net (code "63") (name "unconnected-(U2-CBUS3-Pad14)") (class "Default")
      (node (ref "U2") (pin "14") (pinfunction "CBUS3_14") (pintype "passive+no_connect"))
    )
    (net (code "64") (name "unconnected-(U2-CBUS4-Pad12)") (class "Default")
      (node (ref "U2") (pin "12") (pinfunction "CBUS4_12") (pintype "passive+no_connect"))
    )
    (net (code "65") (name "unconnected-(U2-CTS#-Pad11)") (class "Default")
      (node (ref "U2") (pin "11") (pinfunction "CTS#_11") (pintype "passive+no_connect"))
    )
    (net (code "66") (name "unconnected-(U2-DCD#-Pad10)") (class "Default")
      (node (ref "U2") (pin "10") (pinfunction "DCD#_10") (pintype "passive+no_connect"))
    )
    (net (code "67") (name "unconnected-(U2-DSR#-Pad9)") (class "Default")
      (node (ref "U2") (pin "9") (pinfunction "DSR#_9") (pintype "passive+no_connect"))
    )
    (net (code "68") (name "unconnected-(U2-NC-Pad8)") (class "Default")
      (node (ref "U2") (pin "8") (pinfunction "NC_8") (pintype "passive+no_connect"))
    )
    (net (code "69") (name "unconnected-(U2-NC-Pad24)") (class "Default")
      (node (ref "U2") (pin "24") (pinfunction "NC_24") (pintype "passive+no_connect"))
    )
    (net (code "70") (name "unconnected-(U2-OSCI-Pad27)") (class "Default")
      (node (ref "U2") (pin "27") (pinfunction "OSCI_27") (pintype "passive+no_connect"))
    )
    (net (code "71") (name "unconnected-(U2-OSCO-Pad28)") (class "Default")
      (node (ref "U2") (pin "28") (pinfunction "OSCO_28") (pintype "passive+no_connect"))
    )
    (net (code "72") (name "unconnected-(U2-RESET#-Pad19)") (class "Default")
      (node (ref "U2") (pin "19") (pinfunction "RESET#_19") (pintype "passive+no_connect"))
    )
    (net (code "73") (name "unconnected-(U2-RI#-Pad6)") (class "Default")
      (node (ref "U2") (pin "6") (pinfunction "RI#_6") (pintype "passive+no_connect"))
    )
    (net (code "74") (name "unconnected-(U2-RTS#-Pad3)") (class "Default")
      (node (ref "U2") (pin "3") (pinfunction "RTS#_3") (pintype "passive+no_connect"))
    )
    (net (code "75") (name "unconnected-(ts1-EP-Pad21)") (class "Default")
      (node (ref "ts1") (pin "21") (pinfunction "EP_21") (pintype "power_in+no_connect"))
    )
    (net (code "76") (name "unconnected-(ts1-~{IRQ}-Pad6)") (class "Default")
      (node (ref "ts1") (pin "6") (pinfunction "~{IRQ}_6") (pintype "output+no_connect"))
    )
  )
)
